# LIMIT_SWITCH.net
KiCad netlist of a schematic drawn in Altium Designer
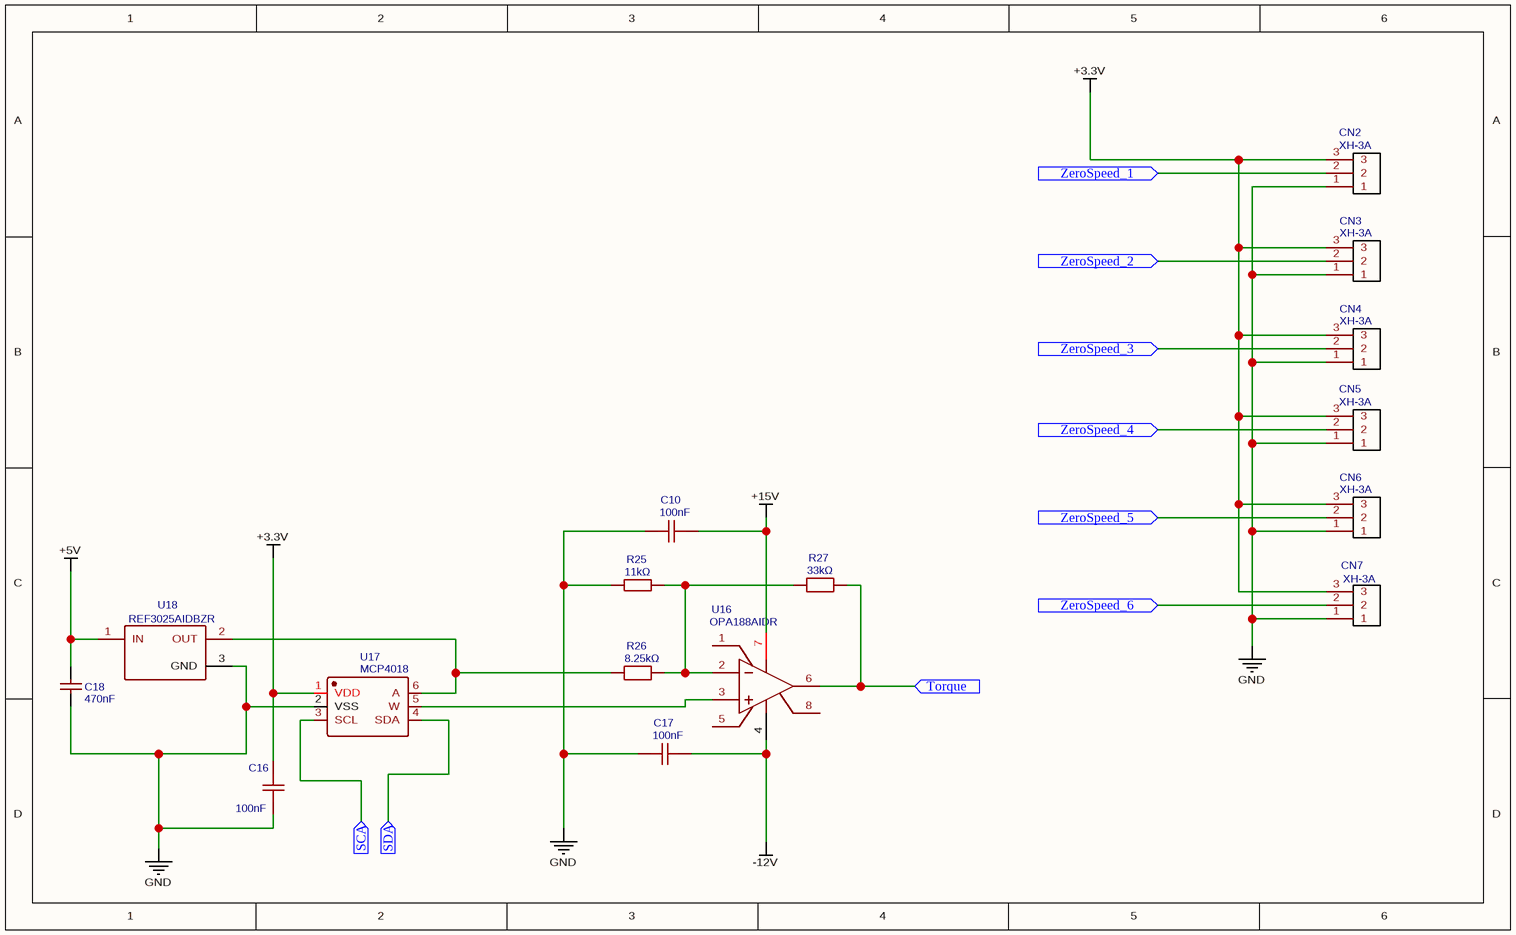
[diagram p0: LIMIT_SWITCH.schdoc]

(export (version "E")
  (design (tool "Eeschema 10.0.6"))
  (components
    (comp (ref "C10")
      (value "100nF")
      (fields
        (field (name "MANUFACTURER") "YAGEO")
        (field (name "MANUFACTURER PART") "CC0805KRX7R8BB104")
        (field (name "CONTRIBUTOR") "LCSC")
      )
      (libsource (lib "altium-import") (part "root_2_100nF_"))
    )
    (comp (ref "C16")
      (value "100nF")
      (fields
        (field (name "MANUFACTURER") "YAGEO")
        (field (name "MANUFACTURER PART") "CC0805KRX7R8BB104")
        (field (name "CONTRIBUTOR") "LCSC")
      )
      (libsource (lib "altium-import") (part "root_1_100nF_"))
    )
    (comp (ref "C17")
      (value "100nF")
      (fields
        (field (name "MANUFACTURER") "YAGEO")
        (field (name "MANUFACTURER PART") "CC0805KRX7R8BB104")
        (field (name "CONTRIBUTOR") "LCSC")
      )
      (libsource (lib "altium-import") (part "root_0_100nF_"))
    )
    (comp (ref "C18")
      (value "470nF")
      (fields
        (field (name "MANUFACTURER") "YAGEO(国巨)")
        (field (name "MANUFACTURER PART") "CC0603KRX7R7BB474")
      )
      (libsource (lib "altium-import") (part "root_3_470nF_"))
    )
    (comp (ref "CN2")
      (value "XH-3A")
      (fields (field (name "MANUFACTURER") "BOOMELE(博穆精密)"))
      (libsource (lib "altium-import") (part "root_2_XH-3A_"))
    )
    (comp (ref "CN3")
      (value "XH-3A")
      (fields (field (name "MANUFACTURER") "BOOMELE(博穆精密)"))
      (libsource (lib "altium-import") (part "root_2_XH-3A_"))
    )
    (comp (ref "CN4")
      (value "XH-3A")
      (fields (field (name "MANUFACTURER") "BOOMELE(博穆精密)"))
      (libsource (lib "altium-import") (part "root_2_XH-3A_"))
    )
    (comp (ref "CN5")
      (value "XH-3A")
      (fields (field (name "MANUFACTURER") "BOOMELE(博穆精密)"))
      (libsource (lib "altium-import") (part "root_2_XH-3A_"))
    )
    (comp (ref "CN6")
      (value "XH-3A")
      (fields (field (name "MANUFACTURER") "BOOMELE(博穆精密)"))
      (libsource (lib "altium-import") (part "root_2_XH-3A_"))
    )
    (comp (ref "CN7")
      (value "XH-3A")
      (fields (field (name "MANUFACTURER") "BOOMELE(博穆精密)"))
      (libsource (lib "altium-import") (part "root_0_XH-3A_"))
    )
    (comp (ref "R25")
      (value "11kΩ")
      (fields
        (field (name "MANUFACTURER") "Viking(光颉)")
        (field (name "MANUFACTURER PART") "ARG03FTC1102")
        (field (name "CONTRIBUTOR") "LCSC")
      )
      (libsource (lib "altium-import") (part "root_0_11kΩ_"))
    )
    (comp (ref "R26")
      (value "8.25kΩ")
      (fields
        (field (name "MANUFACTURER") "YAGEO(国巨)")
        (field (name "MANUFACTURER PART") "RT0603BRD078K25L")
        (field (name "CONTRIBUTOR") "LCSC")
      )
      (libsource (lib "altium-import") (part "root_2_8.25kΩ_"))
    )
    (comp (ref "R27")
      (value "33kΩ")
      (fields
        (field (name "MANUFACTURER") "YAGEO(国巨)")
        (field (name "MANUFACTURER PART") "RT0603BRD0733KL")
        (field (name "CONTRIBUTOR") "LCSC")
      )
      (libsource (lib "altium-import") (part "root_0_33kΩ_"))
    )
    (comp (ref "U16")
      (value "OPA188AIDR")
      (fields (field (name "MANUFACTURER") "TI(德州仪器)") (field (name "CONTRIBUTOR") "LCSC"))
      (libsource (lib "altium-import") (part "root_0_OPA188AIDR_"))
    )
    (comp (ref "U17")
      (value "MCP4018")
      (fields
        (field (name "MANUFACTURER") "MICROCHIP(美国微芯)")
        (field (name "MANUFACTURER PART") "MCP4018T-503E/LT")
        (field (name "CONTRIBUTOR") "LCSC")
      )
      (libsource (lib "altium-import") (part "root_0_MCP4018_"))
    )
    (comp (ref "U18")
      (value "REF3025AIDBZR")
      (fields (field (name "MANUFACTURER") "TI(德州仪器)"))
      (libsource (lib "altium-import") (part "root_0_REF3025AIDBZR_"))
    )
  )
  (nets
    (net (code "1") (name "+3.3V") (class "Default")
      (node (ref "C16") (pin "2") (pinfunction "2_2") (pintype "passive"))
      (node (ref "CN2") (pin "3") (pinfunction "3_3") (pintype "passive"))
      (node (ref "CN3") (pin "3") (pinfunction "3_3") (pintype "passive"))
      (node (ref "CN4") (pin "3") (pinfunction "3_3") (pintype "passive"))
      (node (ref "CN5") (pin "3") (pinfunction "3_3") (pintype "passive"))
      (node (ref "CN6") (pin "3") (pinfunction "3_3") (pintype "passive"))
      (node (ref "CN7") (pin "3") (pinfunction "3_3") (pintype "passive"))
      (node (ref "U17") (pin "1") (pinfunction "VDD_1") (pintype "passive"))
    )
    (net (code "2") (name "+5V") (class "Default")
      (node (ref "C18") (pin "1") (pinfunction "1_1") (pintype "passive"))
      (node (ref "U18") (pin "1") (pinfunction "IN_1") (pintype "passive"))
    )
    (net (code "3") (name "+15V") (class "Default")
      (node (ref "C10") (pin "1") (pinfunction "1_1") (pintype "passive"))
      (node (ref "U16") (pin "7") (pinfunction "V+_7") (pintype "passive"))
    )
    (net (code "4") (name "-12V") (class "Default")
      (node (ref "C17") (pin "2") (pinfunction "2_2") (pintype "passive"))
      (node (ref "U16") (pin "4") (pinfunction "V-_4") (pintype "passive"))
    )
    (net (code "5") (name "/SCA") (class "Default")
      (node (ref "U17") (pin "3") (pinfunction "SCL_3") (pintype "passive"))
    )
    (net (code "6") (name "/SDA") (class "Default")
      (node (ref "U17") (pin "4") (pinfunction "SDA_4") (pintype "passive"))
    )
    (net (code "7") (name "/Torque") (class "Default")
      (node (ref "R27") (pin "2") (pinfunction "2_2") (pintype "passive"))
      (node (ref "U16") (pin "6") (pinfunction "OUT_6") (pintype "passive"))
    )
    (net (code "8") (name "/ZeroSpeed_1") (class "Default")
      (node (ref "CN2") (pin "2") (pinfunction "2_2") (pintype "passive"))
    )
    (net (code "9") (name "/ZeroSpeed_2") (class "Default")
      (node (ref "CN3") (pin "2") (pinfunction "2_2") (pintype "passive"))
    )
    (net (code "10") (name "/ZeroSpeed_3") (class "Default")
      (node (ref "CN4") (pin "2") (pinfunction "2_2") (pintype "passive"))
    )
    (net (code "11") (name "/ZeroSpeed_4") (class "Default")
      (node (ref "CN5") (pin "2") (pinfunction "2_2") (pintype "passive"))
    )
    (net (code "12") (name "/ZeroSpeed_5") (class "Default")
      (node (ref "CN6") (pin "2") (pinfunction "2_2") (pintype "passive"))
    )
    (net (code "13") (name "/ZeroSpeed_6") (class "Default")
      (node (ref "CN7") (pin "2") (pinfunction "2_2") (pintype "passive"))
    )
    (net (code "14") (name "GND") (class "Default")
      (node (ref "C10") (pin "2") (pinfunction "2_2") (pintype "passive"))
      (node (ref "C16") (pin "1") (pinfunction "1_1") (pintype "passive"))
      (node (ref "C17") (pin "1") (pinfunction "1_1") (pintype "passive"))
      (node (ref "C18") (pin "2") (pinfunction "2_2") (pintype "passive"))
      (node (ref "CN2") (pin "1") (pinfunction "1_1") (pintype "passive"))
      (node (ref "CN3") (pin "1") (pinfunction "1_1") (pintype "passive"))
      (node (ref "CN4") (pin "1") (pinfunction "1_1") (pintype "passive"))
      (node (ref "CN5") (pin "1") (pinfunction "1_1") (pintype "passive"))
      (node (ref "CN6") (pin "1") (pinfunction "1_1") (pintype "passive"))
      (node (ref "CN7") (pin "1") (pinfunction "1_1") (pintype "passive"))
      (node (ref "R25") (pin "1") (pinfunction "1_1") (pintype "passive"))
      (node (ref "U17") (pin "2") (pinfunction "VSS_2") (pintype "passive"))
      (node (ref "U18") (pin "3") (pinfunction "GND_3") (pintype "passive"))
    )
    (net (code "15") (name "Net-(U16-IN+)") (class "Default")
      (node (ref "U16") (pin "3") (pinfunction "IN+_3") (pintype "passive"))
      (node (ref "U17") (pin "5") (pinfunction "W_5") (pintype "passive"))
    )
    (net (code "16") (name "Net-(U16-IN-)") (class "Default")
      (node (ref "R25") (pin "2") (pinfunction "2_2") (pintype "passive"))
      (node (ref "R26") (pin "1") (pinfunction "1_1") (pintype "passive"))
      (node (ref "R27") (pin "1") (pinfunction "1_1") (pintype "passive"))
      (node (ref "U16") (pin "2") (pinfunction "IN-_2") (pintype "passive"))
    )
    (net (code "17") (name "Net-(U17-A)") (class "Default")
      (node (ref "R26") (pin "2") (pinfunction "2_2") (pintype "passive"))
      (node (ref "U17") (pin "6") (pinfunction "A_6") (pintype "passive"))
      (node (ref "U18") (pin "2") (pinfunction "OUT_2") (pintype "passive"))
    )
    (net (code "18") (name "unconnected-(U16-NC-Pad1)") (class "Default")
      (node (ref "U16") (pin "1") (pinfunction "NC_1") (pintype "passive"))
    )
    (net (code "19") (name "unconnected-(U16-NC-Pad5)") (class "Default")
      (node (ref "U16") (pin "5") (pinfunction "NC_5") (pintype "passive"))
    )
    (net (code "20") (name "unconnected-(U16-NC-Pad8)") (class "Default")
      (node (ref "U16") (pin "8") (pinfunction "NC_8") (pintype "passive"))
    )
  )
)
